# currentsource.net
KiCad netlist of a schematic drawn in Altium Designer
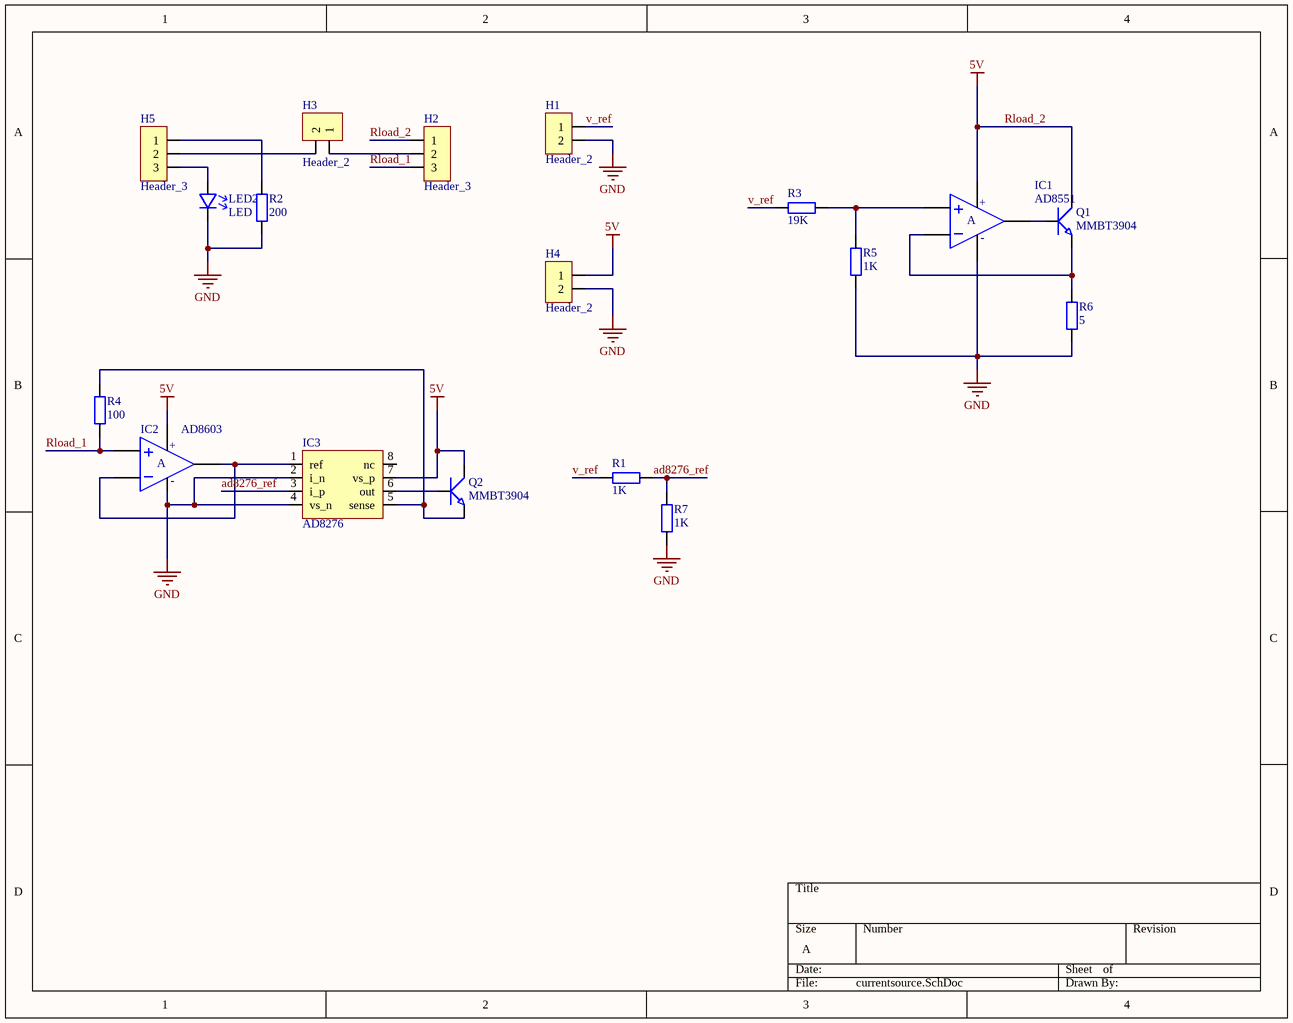
[diagram p0: currentsource.SchDoc]

(export (version "E")
  (design (tool "Eeschema 10.0.6"))
  (components
    (comp (ref "H1")
      (value "Header_2")
      (footprint "Header_Male_2_right")
      (description "Generic 2pin header symbol")
      (libsource (lib "AranCustomFootprints") (part "Header_2"))
    )
    (comp (ref "H2")
      (value "Header_3")
      (footprint "Header_MALE_3")
      (description "Generic 3pin header symbol")
      (libsource (lib "") (part "Header_3_1"))
    )
    (comp (ref "H3")
      (value "Header_2")
      (footprint "Header_Male_2_right")
      (description "Generic 2pin header symbol")
      (libsource (lib "") (part "Header_2_1"))
    )
    (comp (ref "H4")
      (value "Header_2")
      (footprint "Header_Male_2_right")
      (description "Generic 2pin header symbol")
      (libsource (lib "AranCustomFootprints") (part "Header_2"))
    )
    (comp (ref "H5")
      (value "Header_3")
      (footprint "Header_MALE_3")
      (description "Generic 3pin header symbol")
      (libsource (lib "AranCustomFootprints") (part "Header_3"))
    )
    (comp (ref "IC1")
      (value "AD8551")
      (footprint "8-SOIC")
      (description "Zero  -Drift, Single  -Supply, Rail  -to-Rail   Input/Output Operational Amplifiers")
      (libsource (lib "elmarlib") (part "AD8551ARZ"))
    )
    (comp (ref "IC2")
      (value "AD8603")
      (footprint "5-TSOT")
      (description "Rail-to-Rail Input/Output Operational Amplifier")
      (libsource (lib "elmarlib") (part "AD8603AUJZ"))
    )
    (comp (ref "IC3")
      (value "AD8276")
      (footprint "8-SOIC")
      (description "Unity-Gain Difference Amplifier")
      (libsource (lib "elmarlib") (part "AD8276ARZ"))
    )
    (comp (ref "LED2")
      (value "LED")
      (footprint "LED_5MM_TROUGH")
      (description "Schematic symbol of a LED")
      (libsource (lib "AranCustomFootprints") (part "LED"))
    )
    (comp (ref "Q1")
      (value "MMBT3904")
      (footprint "3-SOT-23")
      (description "40V NPN SMALL SIGNAL TRANSISTOR IN SOT23")
      (libsource (lib "elmarlib") (part "MMBT3904"))
    )
    (comp (ref "Q2")
      (value "MMBT3904")
      (footprint "3-SOT-23")
      (description "40V NPN SMALL SIGNAL TRANSISTOR IN SOT23")
      (libsource (lib "elmarlib") (part "MMBT3904"))
    )
    (comp (ref "R1")
      (value "1K")
      (footprint "R0805")
      (description "Schematic symbol of a resistor")
      (libsource (lib "AranCustomFootprints") (part "Resistor"))
    )
    (comp (ref "R2")
      (value "200")
      (footprint "R0805")
      (description "Schematic symbol of a resistor")
      (libsource (lib "AranCustomFootprints") (part "Resistor"))
    )
    (comp (ref "R3")
      (value "19K")
      (footprint "R0805")
      (description "Schematic symbol of a resistor")
      (libsource (lib "AranCustomFootprints") (part "Resistor"))
    )
    (comp (ref "R4")
      (value "100")
      (footprint "R0805")
      (description "Schematic symbol of a resistor")
      (libsource (lib "AranCustomFootprints") (part "Resistor"))
    )
    (comp (ref "R5")
      (value "1K")
      (footprint "R0805")
      (description "Schematic symbol of a resistor")
      (libsource (lib "AranCustomFootprints") (part "Resistor"))
    )
    (comp (ref "R6")
      (value "5")
      (footprint "R0805")
      (description "Schematic symbol of a resistor")
      (libsource (lib "AranCustomFootprints") (part "Resistor"))
    )
    (comp (ref "R7")
      (value "1K")
      (footprint "R0805")
      (description "Schematic symbol of a resistor")
      (libsource (lib "AranCustomFootprints") (part "Resistor"))
    )
  )
  (nets
    (net (code "1") (name "/Rload_1") (class "Default")
      (node (ref "H2") (pin "3") (pinfunction "3_3") (pintype "passive"))
      (node (ref "IC2") (pin "3") (pinfunction "+_3") (pintype "passive"))
      (node (ref "R4") (pin "1") (pinfunction "1_1") (pintype "passive"))
    )
    (net (code "2") (name "/ad8276_ref") (class "Default")
      (node (ref "IC3") (pin "3") (pinfunction "i_p_3") (pintype "passive"))
      (node (ref "R1") (pin "2") (pinfunction "2_2") (pintype "passive"))
      (node (ref "R7") (pin "1") (pinfunction "1_1") (pintype "passive"))
    )
    (net (code "3") (name "/v_ref") (class "Default")
      (node (ref "H1") (pin "1") (pinfunction "1_1") (pintype "passive"))
      (node (ref "R1") (pin "1") (pinfunction "1_1") (pintype "passive"))
      (node (ref "R3") (pin "1") (pinfunction "1_1") (pintype "passive"))
    )
    (net (code "4") (name "5V") (class "Default")
      (node (ref "H2") (pin "1") (pinfunction "1_1") (pintype "passive"))
      (node (ref "H4") (pin "1") (pinfunction "1_1") (pintype "passive"))
      (node (ref "IC1") (pin "7") (pinfunction "V+_7") (pintype "passive"))
      (node (ref "IC2") (pin "5") (pinfunction "V+_5") (pintype "passive"))
      (node (ref "IC3") (pin "7") (pinfunction "vs_p_7") (pintype "passive"))
      (node (ref "Q1") (pin "3") (pinfunction "Source_3") (pintype "passive"))
      (node (ref "Q2") (pin "3") (pinfunction "Source_3") (pintype "passive"))
    )
    (net (code "5") (name "GND") (class "Default")
      (node (ref "H1") (pin "2") (pinfunction "2_2") (pintype "passive"))
      (node (ref "H4") (pin "2") (pinfunction "2_2") (pintype "passive"))
      (node (ref "IC1") (pin "4") (pinfunction "V-_4") (pintype "passive"))
      (node (ref "IC2") (pin "2") (pinfunction "V-_2") (pintype "passive"))
      (node (ref "IC3") (pin "2") (pinfunction "i_n_2") (pintype "passive"))
      (node (ref "IC3") (pin "4") (pinfunction "vs_n_4") (pintype "passive"))
      (node (ref "LED2") (pin "C") (pinfunction "Cathode_C") (pintype "passive"))
      (node (ref "R2") (pin "2") (pinfunction "2_2") (pintype "passive"))
      (node (ref "R5") (pin "1") (pinfunction "1_1") (pintype "passive"))
      (node (ref "R6") (pin "2") (pinfunction "2_2") (pintype "passive"))
      (node (ref "R7") (pin "2") (pinfunction "2_2") (pintype "passive"))
    )
    (net (code "6") (name "Net-(H2-Pad2)") (class "Default")
      (node (ref "H2") (pin "2") (pinfunction "2_2") (pintype "passive"))
      (node (ref "H3") (pin "1") (pinfunction "1_1") (pintype "passive"))
    )
    (net (code "7") (name "Net-(H3-Pad2)") (class "Default")
      (node (ref "H3") (pin "2") (pinfunction "2_2") (pintype "passive"))
      (node (ref "H5") (pin "2") (pinfunction "2_2") (pintype "passive"))
    )
    (net (code "8") (name "Net-(H5-Pad1)") (class "Default")
      (node (ref "H5") (pin "1") (pinfunction "1_1") (pintype "passive"))
      (node (ref "R2") (pin "1") (pinfunction "1_1") (pintype "passive"))
    )
    (net (code "9") (name "Net-(IC1-+)") (class "Default")
      (node (ref "IC1") (pin "3") (pinfunction "+_3") (pintype "passive"))
      (node (ref "R3") (pin "2") (pinfunction "2_2") (pintype "passive"))
      (node (ref "R5") (pin "2") (pinfunction "2_2") (pintype "passive"))
    )
    (net (code "10") (name "Net-(IC1--)") (class "Default")
      (node (ref "IC1") (pin "2") (pinfunction "-_2") (pintype "passive"))
      (node (ref "Q1") (pin "2") (pinfunction "Emitter_2") (pintype "passive"))
      (node (ref "R6") (pin "1") (pinfunction "1_1") (pintype "passive"))
    )
    (net (code "11") (name "Net-(IC1-6)") (class "Default")
      (node (ref "IC1") (pin "1") (pinfunction "6_1") (pintype "passive"))
      (node (ref "Q1") (pin "1") (pinfunction "Base_1") (pintype "passive"))
    )
    (net (code "12") (name "Net-(IC2--)") (class "Default")
      (node (ref "IC2") (pin "1") (pinfunction "OUT_1") (pintype "passive"))
      (node (ref "IC2") (pin "4") (pinfunction "-_4") (pintype "passive"))
      (node (ref "IC3") (pin "1") (pinfunction "ref_1") (pintype "passive"))
    )
    (net (code "13") (name "Net-(IC3-out)") (class "Default")
      (node (ref "IC3") (pin "6") (pinfunction "out_6") (pintype "passive"))
      (node (ref "Q2") (pin "1") (pinfunction "Base_1") (pintype "passive"))
    )
    (net (code "14") (name "Net-(IC3-sense)") (class "Default")
      (node (ref "IC3") (pin "5") (pinfunction "sense_5") (pintype "passive"))
      (node (ref "Q2") (pin "2") (pinfunction "Emitter_2") (pintype "passive"))
      (node (ref "R4") (pin "2") (pinfunction "2_2") (pintype "passive"))
    )
    (net (code "15") (name "Net-(LED2-Anode)") (class "Default")
      (node (ref "H5") (pin "3") (pinfunction "3_3") (pintype "passive"))
      (node (ref "LED2") (pin "A") (pinfunction "Anode_A") (pintype "passive"))
    )
    (net (code "16") (name "unconnected-(IC3-nc-Pad8)") (class "Default")
      (node (ref "IC3") (pin "8") (pinfunction "nc_8") (pintype "passive"))
    )
  )
)
